# EDev.net
KiCad netlist of a schematic drawn in EasyEDA Pro
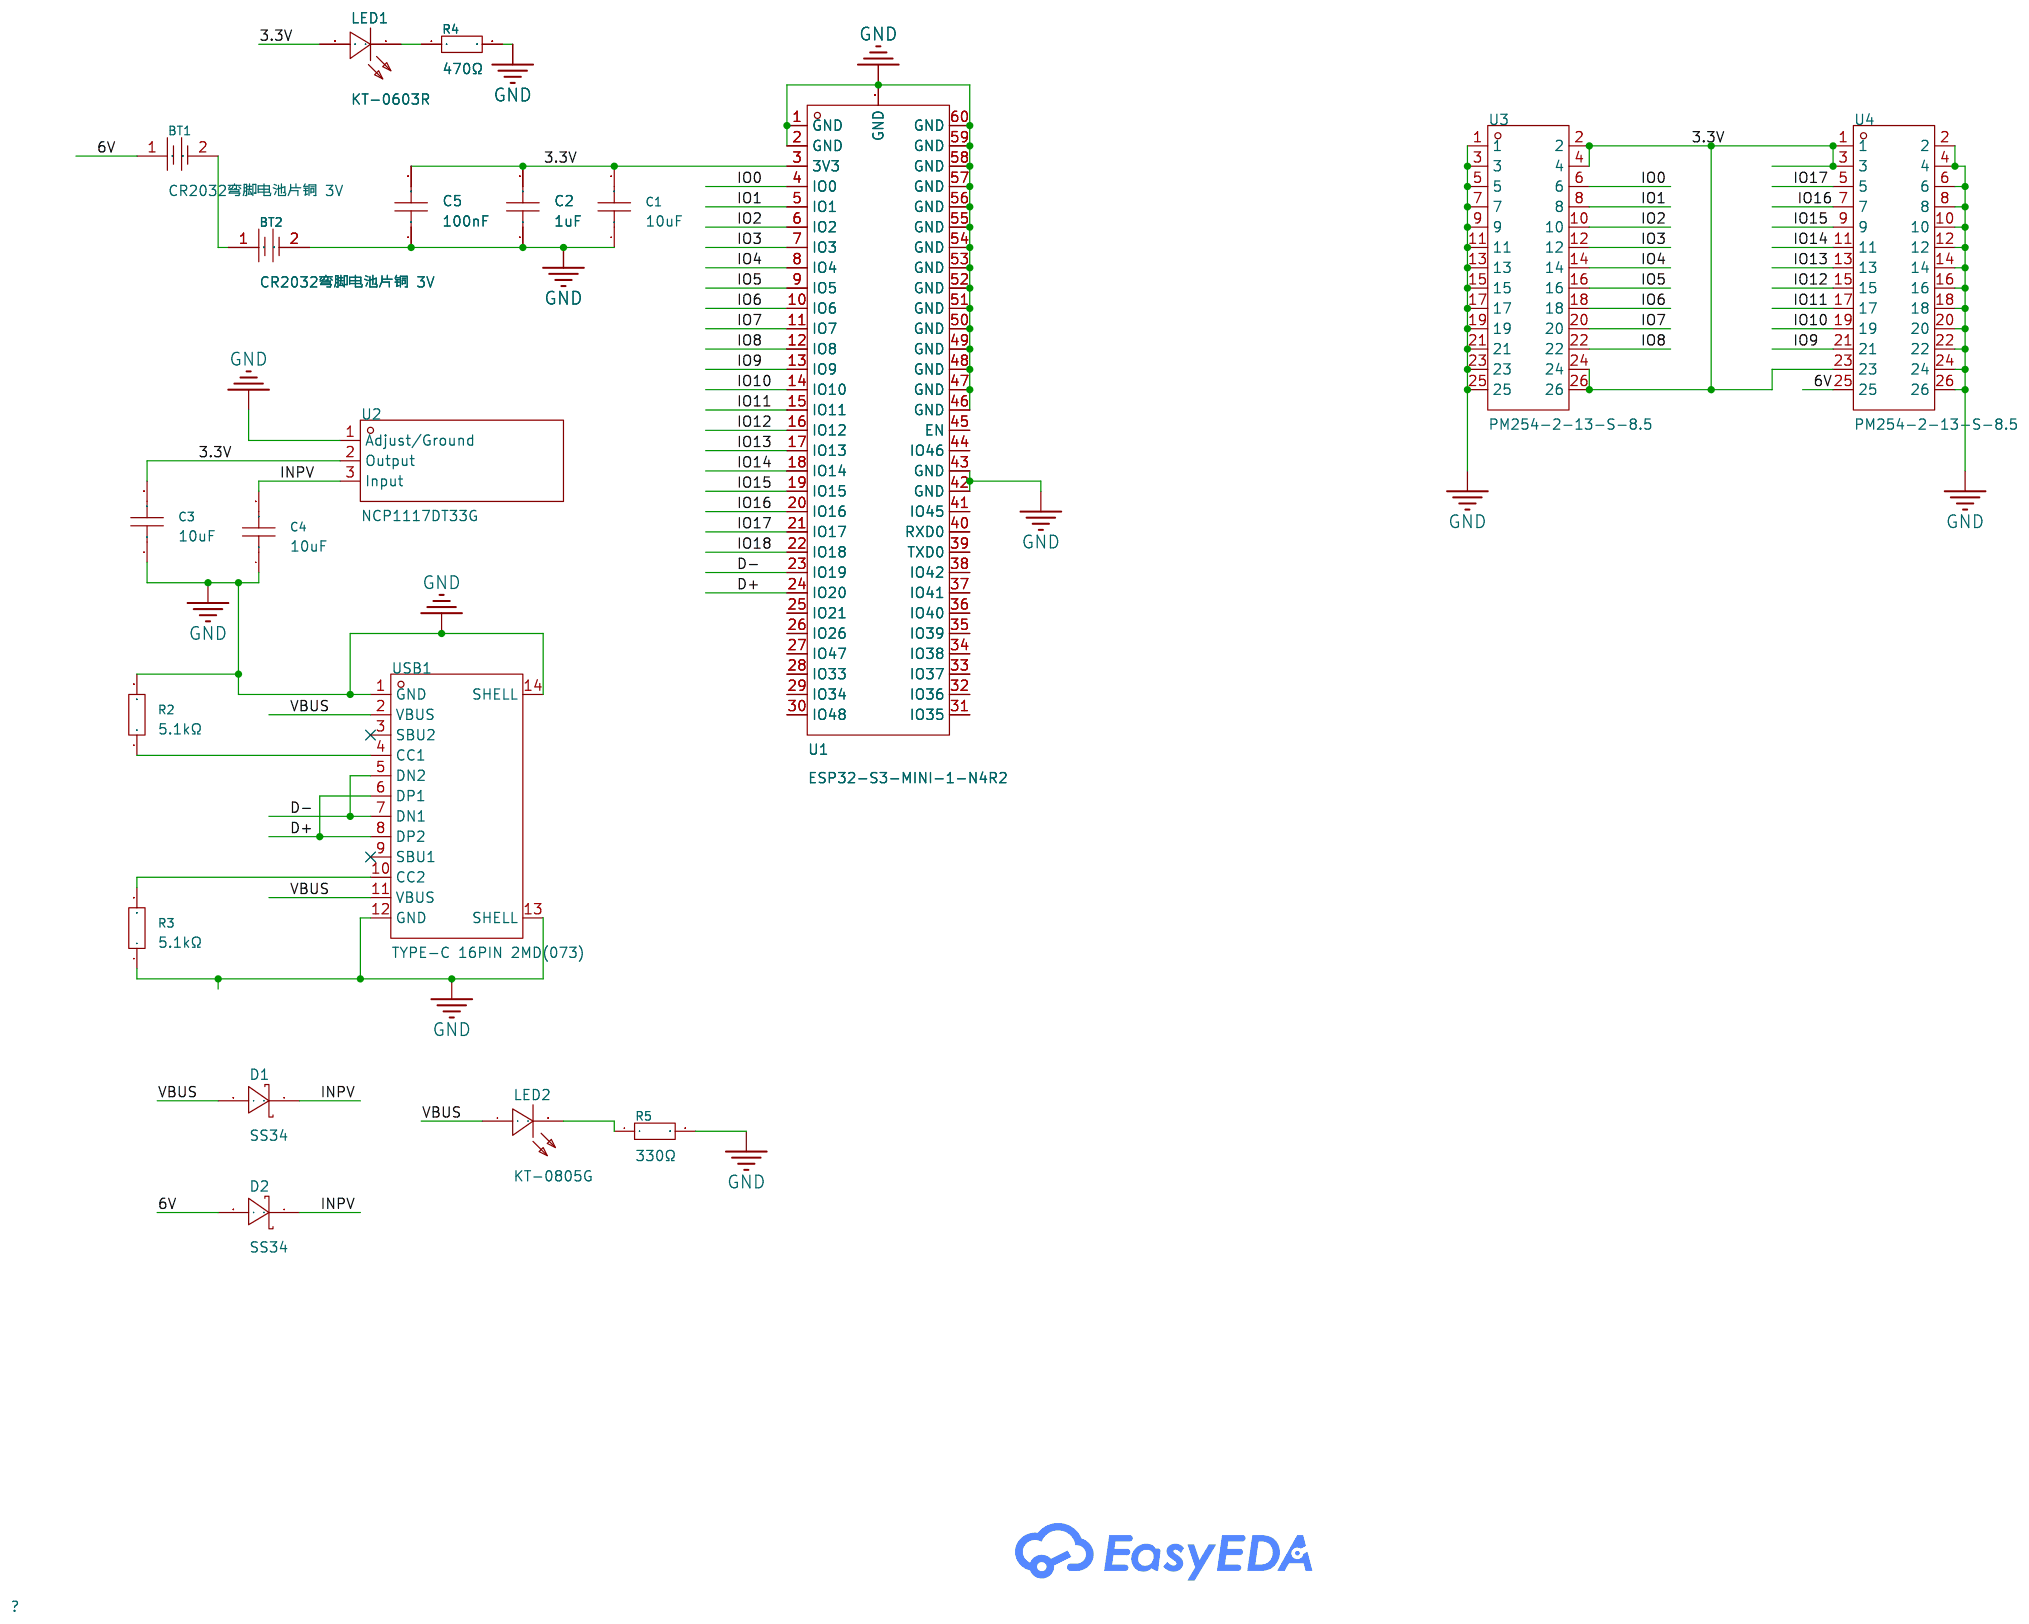
[diagram p0: schematic sheet]

(export (version "E")
  (design (tool "Eeschema 10.0.6"))
  (components
    (comp (ref "BT1")
      (value "CR2032弯脚电池片铜 3V")
      (footprint "easyedapro:BAT-SMD_CR2032-3V")
      (fields (field (name "Manufacturer") "Q&J"))
      (libsource (lib "easyedapro") (part "C70373"))
    )
    (comp (ref "BT2")
      (value "CR2032弯脚电池片铜 3V")
      (footprint "easyedapro:BAT-SMD_CR2032-3V")
      (fields (field (name "Manufacturer") "Q&J"))
      (libsource (lib "easyedapro") (part "C70373"))
    )
    (comp (ref "C1")
      (value "10uF")
      (footprint "easyedapro:C0603")
      (fields
        (field (name "Manufacturer Part") "CL10A106MA8NRNC")
        (field (name "Manufacturer") "SAMSUNG(三星)")
      )
      (libsource (lib "easyedapro") (part "CL10A106MA8NRNC"))
    )
    (comp (ref "C2")
      (value "1uF")
      (footprint "easyedapro:C0603")
      (fields
        (field (name "Manufacturer Part") "CL10A105KB8NNNC")
        (field (name "Manufacturer") "SAMSUNG(三星)")
      )
      (libsource (lib "easyedapro") (part "CL10A105KB8NNNC"))
    )
    (comp (ref "C3")
      (value "10uF")
      (footprint "easyedapro:C0603")
      (fields
        (field (name "Manufacturer Part") "CL10A106MA8NRNC")
        (field (name "Manufacturer") "SAMSUNG(三星)")
      )
      (libsource (lib "easyedapro") (part "CL10A106MA8NRNC"))
    )
    (comp (ref "C4")
      (value "10uF")
      (footprint "easyedapro:C0603")
      (fields
        (field (name "Manufacturer Part") "CL10A106MA8NRNC")
        (field (name "Manufacturer") "SAMSUNG(三星)")
      )
      (libsource (lib "easyedapro") (part "CL10A106MA8NRNC"))
    )
    (comp (ref "C5")
      (value "100nF")
      (footprint "easyedapro:C0402")
      (fields
        (field (name "Manufacturer Part") "CL05B104KO5NNNC")
        (field (name "Manufacturer") "SAMSUNG(三星)")
      )
      (libsource (lib "easyedapro") (part "CL05B104KO5NNNC"))
    )
    (comp (ref "D1")
      (value "SS34")
      (footprint "easyedapro:SMA_L4.3-W2.6-LS5.2-RD")
      (fields (field (name "Manufacturer") "MDD(辰达半导体)"))
      (libsource (lib "easyedapro") (part "SS34_C8678"))
    )
    (comp (ref "D2")
      (value "SS34")
      (footprint "easyedapro:SMA_L4.3-W2.6-LS5.2-RD")
      (fields (field (name "Manufacturer") "MDD(辰达半导体)"))
      (libsource (lib "easyedapro") (part "SS34_C8678"))
    )
    (comp (ref "LED1")
      (value "KT-0603R")
      (footprint "easyedapro:LED0603-RD")
      (fields (field (name "Manufacturer") "KENTO"))
      (libsource (lib "easyedapro") (part "KT-0603R"))
    )
    (comp (ref "LED2")
      (value "KT-0805G")
      (footprint "easyedapro:LED0805-R-RD")
      (fields (field (name "Manufacturer") "KENTO"))
      (libsource (lib "easyedapro") (part "0805G (Green)"))
    )
    (comp (ref "R2")
      (value "5.1kΩ")
      (footprint "easyedapro:R0402")
      (fields
        (field (name "Manufacturer Part") "0402WGF5101TCE")
        (field (name "Manufacturer") "UNI-ROYAL(厚声)")
      )
      (libsource (lib "easyedapro") (part "0402WGF5101TCE"))
    )
    (comp (ref "R3")
      (value "5.1kΩ")
      (footprint "easyedapro:R0402")
      (fields
        (field (name "Manufacturer Part") "0402WGF5101TCE")
        (field (name "Manufacturer") "UNI-ROYAL(厚声)")
      )
      (libsource (lib "easyedapro") (part "0402WGF5101TCE"))
    )
    (comp (ref "R4")
      (value "470Ω")
      (footprint "easyedapro:R0805")
      (fields
        (field (name "Manufacturer Part") "0805W8F4700T5E")
        (field (name "Manufacturer") "UNI-ROYAL(厚声)")
      )
      (libsource (lib "easyedapro") (part "0805W8F4700T5E"))
    )
    (comp (ref "R5")
      (value "330Ω")
      (footprint "easyedapro:R0805")
      (fields
        (field (name "Manufacturer Part") "0805W8F3300T5E")
        (field (name "Manufacturer") "UNI-ROYAL(厚声)")
      )
      (libsource (lib "easyedapro") (part "0805W8F3300T5E"))
    )
    (comp (ref "U1")
      (value "ESP32-S3-MINI-1-N4R2")
      (footprint "easyedapro:BULETM-SMD_ESP32-S3-MINI-1-N8")
      (description "Antenna Type:On-Board PCB Antenna")
      (fields (field (name "Manufacturer") "ESPRESSIF(乐鑫)"))
      (libsource (lib "easyedapro") (part "ESP32-S3-MINI-1-N4R2"))
    )
    (comp (ref "U2")
      (value "NCP1117DT33G")
      (footprint "easyedapro:TO-252_L6.5-W6.1-P4.58-LS9.9-BR")
      (fields (field (name "Manufacturer") "onsemi(安森美)"))
      (libsource (lib "easyedapro") (part "NCP1117DT33G"))
    )
    (comp (ref "U3")
      (value "PM254-2-13-S-8.5")
      (footprint "easyedapro:HDR-SMD_26P-P2.54-V-F-R2-C13-LS7.2")
      (fields (field (name "Manufacturer") "HCTL(华灿天禄)"))
      (libsource (lib "easyedapro") (part "PM254-2-13-S-8.5"))
    )
    (comp (ref "U4")
      (value "PM254-2-13-S-8.5")
      (footprint "easyedapro:HDR-SMD_26P-P2.54-V-F-R2-C13-LS7.2")
      (fields (field (name "Manufacturer") "HCTL(华灿天禄)"))
      (libsource (lib "easyedapro") (part "PM254-2-13-S-8.5"))
    )
    (comp (ref "USB1")
      (value "TYPE-C 16PIN 2MD(073)")
      (footprint "easyedapro:USB-C-SMD_TYPE-C-6PIN-2MD-073")
      (fields (field (name "Manufacturer") "SHOU HAN(首韩)"))
      (libsource (lib "easyedapro") (part "TYPE-C 16PIN 2MD(073)"))
    )
  )
  (nets
    (net (code "1") (name "/3.3V") (class "Default")
      (node (ref "C1") (pin "2") (pinfunction "2_2") (pintype "input"))
      (node (ref "C2") (pin "2") (pinfunction "2_2") (pintype "unspecified"))
      (node (ref "C3") (pin "2") (pinfunction "2_2") (pintype "input"))
      (node (ref "C5") (pin "2") (pinfunction "2_2") (pintype "unspecified"))
      (node (ref "LED1") (pin "2") (pinfunction "A_2") (pintype "unspecified"))
      (node (ref "U1") (pin "3") (pinfunction "3V3_3") (pintype "unspecified"))
      (node (ref "U2") (pin "2") (pinfunction "Output_2") (pintype "unspecified"))
      (node (ref "U3") (pin "2") (pinfunction "2_2") (pintype "unspecified"))
      (node (ref "U3") (pin "24") (pinfunction "24_24") (pintype "unspecified"))
      (node (ref "U3") (pin "26") (pinfunction "26_26") (pintype "unspecified"))
      (node (ref "U3") (pin "4") (pinfunction "4_4") (pintype "unspecified"))
      (node (ref "U4") (pin "1") (pinfunction "1_1") (pintype "unspecified"))
      (node (ref "U4") (pin "23") (pinfunction "23_23") (pintype "unspecified"))
      (node (ref "U4") (pin "3") (pinfunction "3_3") (pintype "unspecified"))
    )
    (net (code "2") (name "/6V") (class "Default")
      (node (ref "BT1") (pin "1") (pinfunction "1_1") (pintype "input"))
      (node (ref "D2") (pin "2") (pinfunction "A_2") (pintype "unspecified"))
      (node (ref "U4") (pin "25") (pinfunction "25_25") (pintype "unspecified"))
    )
    (net (code "3") (name "/D+") (class "Default")
      (node (ref "U1") (pin "24") (pinfunction "IO20_24") (pintype "unspecified"))
      (node (ref "USB1") (pin "6") (pinfunction "DP1_6") (pintype "unspecified"))
      (node (ref "USB1") (pin "8") (pinfunction "DP2_8") (pintype "unspecified"))
    )
    (net (code "4") (name "/D-") (class "Default")
      (node (ref "U1") (pin "23") (pinfunction "IO19_23") (pintype "unspecified"))
      (node (ref "USB1") (pin "5") (pinfunction "DN2_5") (pintype "unspecified"))
      (node (ref "USB1") (pin "7") (pinfunction "DN1_7") (pintype "unspecified"))
    )
    (net (code "5") (name "/INPV") (class "Default")
      (node (ref "C4") (pin "2") (pinfunction "2_2") (pintype "input"))
      (node (ref "D1") (pin "1") (pinfunction "K_1") (pintype "unspecified"))
      (node (ref "D2") (pin "1") (pinfunction "K_1") (pintype "unspecified"))
      (node (ref "U2") (pin "3") (pinfunction "Input_3") (pintype "unspecified"))
    )
    (net (code "6") (name "/IO0") (class "Default")
      (node (ref "U1") (pin "4") (pinfunction "IO0_4") (pintype "unspecified"))
      (node (ref "U3") (pin "6") (pinfunction "6_6") (pintype "unspecified"))
    )
    (net (code "7") (name "/IO1") (class "Default")
      (node (ref "U1") (pin "5") (pinfunction "IO1_5") (pintype "unspecified"))
      (node (ref "U3") (pin "8") (pinfunction "8_8") (pintype "unspecified"))
    )
    (net (code "8") (name "/IO2") (class "Default")
      (node (ref "U1") (pin "6") (pinfunction "IO2_6") (pintype "unspecified"))
      (node (ref "U3") (pin "10") (pinfunction "10_10") (pintype "unspecified"))
    )
    (net (code "9") (name "/IO3") (class "Default")
      (node (ref "U1") (pin "7") (pinfunction "IO3_7") (pintype "unspecified"))
      (node (ref "U3") (pin "12") (pinfunction "12_12") (pintype "unspecified"))
    )
    (net (code "10") (name "/IO4") (class "Default")
      (node (ref "U1") (pin "8") (pinfunction "IO4_8") (pintype "unspecified"))
      (node (ref "U3") (pin "14") (pinfunction "14_14") (pintype "unspecified"))
    )
    (net (code "11") (name "/IO5") (class "Default")
      (node (ref "U1") (pin "9") (pinfunction "IO5_9") (pintype "unspecified"))
      (node (ref "U3") (pin "16") (pinfunction "16_16") (pintype "unspecified"))
    )
    (net (code "12") (name "/IO6") (class "Default")
      (node (ref "U1") (pin "10") (pinfunction "IO6_10") (pintype "unspecified"))
      (node (ref "U3") (pin "18") (pinfunction "18_18") (pintype "unspecified"))
    )
    (net (code "13") (name "/IO7") (class "Default")
      (node (ref "U1") (pin "11") (pinfunction "IO7_11") (pintype "unspecified"))
      (node (ref "U3") (pin "20") (pinfunction "20_20") (pintype "unspecified"))
    )
    (net (code "14") (name "/IO8") (class "Default")
      (node (ref "U1") (pin "12") (pinfunction "IO8_12") (pintype "unspecified"))
      (node (ref "U3") (pin "22") (pinfunction "22_22") (pintype "unspecified"))
    )
    (net (code "15") (name "/IO9") (class "Default")
      (node (ref "U1") (pin "13") (pinfunction "IO9_13") (pintype "unspecified"))
      (node (ref "U4") (pin "21") (pinfunction "21_21") (pintype "unspecified"))
    )
    (net (code "16") (name "/IO10") (class "Default")
      (node (ref "U1") (pin "14") (pinfunction "IO10_14") (pintype "unspecified"))
      (node (ref "U4") (pin "19") (pinfunction "19_19") (pintype "unspecified"))
    )
    (net (code "17") (name "/IO11") (class "Default")
      (node (ref "U1") (pin "15") (pinfunction "IO11_15") (pintype "unspecified"))
      (node (ref "U4") (pin "17") (pinfunction "17_17") (pintype "unspecified"))
    )
    (net (code "18") (name "/IO12") (class "Default")
      (node (ref "U1") (pin "16") (pinfunction "IO12_16") (pintype "unspecified"))
      (node (ref "U4") (pin "15") (pinfunction "15_15") (pintype "unspecified"))
    )
    (net (code "19") (name "/IO13") (class "Default")
      (node (ref "U1") (pin "17") (pinfunction "IO13_17") (pintype "unspecified"))
      (node (ref "U4") (pin "13") (pinfunction "13_13") (pintype "unspecified"))
    )
    (net (code "20") (name "/IO14") (class "Default")
      (node (ref "U1") (pin "18") (pinfunction "IO14_18") (pintype "unspecified"))
      (node (ref "U4") (pin "11") (pinfunction "11_11") (pintype "unspecified"))
    )
    (net (code "21") (name "/IO15") (class "Default")
      (node (ref "U1") (pin "19") (pinfunction "IO15_19") (pintype "unspecified"))
      (node (ref "U4") (pin "9") (pinfunction "9_9") (pintype "unspecified"))
    )
    (net (code "22") (name "/IO16") (class "Default")
      (node (ref "U1") (pin "20") (pinfunction "IO16_20") (pintype "unspecified"))
      (node (ref "U4") (pin "7") (pinfunction "7_7") (pintype "unspecified"))
    )
    (net (code "23") (name "/IO17") (class "Default")
      (node (ref "U1") (pin "21") (pinfunction "IO17_21") (pintype "unspecified"))
      (node (ref "U4") (pin "5") (pinfunction "5_5") (pintype "unspecified"))
    )
    (net (code "24") (name "/IO18") (class "Default")
      (node (ref "U1") (pin "22") (pinfunction "IO18_22") (pintype "unspecified"))
    )
    (net (code "25") (name "/VBUS") (class "Default")
      (node (ref "D1") (pin "2") (pinfunction "A_2") (pintype "unspecified"))
      (node (ref "LED2") (pin "1") (pinfunction "A_1") (pintype "unspecified"))
      (node (ref "USB1") (pin "11") (pinfunction "VBUS_11") (pintype "unspecified"))
      (node (ref "USB1") (pin "2") (pinfunction "VBUS_2") (pintype "unspecified"))
    )
    (net (code "26") (name "GND") (class "Default")
      (node (ref "BT2") (pin "2") (pinfunction "2_2") (pintype "input"))
      (node (ref "C1") (pin "1") (pinfunction "1_1") (pintype "input"))
      (node (ref "C2") (pin "1") (pinfunction "1_1") (pintype "unspecified"))
      (node (ref "C3") (pin "1") (pinfunction "1_1") (pintype "input"))
      (node (ref "C4") (pin "1") (pinfunction "1_1") (pintype "input"))
      (node (ref "C5") (pin "1") (pinfunction "1_1") (pintype "unspecified"))
      (node (ref "R2") (pin "2") (pinfunction "2_2") (pintype "input"))
      (node (ref "R3") (pin "1") (pinfunction "1_1") (pintype "input"))
      (node (ref "R4") (pin "2") (pinfunction "2_2") (pintype "input"))
      (node (ref "R5") (pin "2") (pinfunction "2_2") (pintype "input"))
      (node (ref "U1") (pin "1") (pinfunction "GND_1") (pintype "unspecified"))
      (node (ref "U1") (pin "2") (pinfunction "GND_2") (pintype "unspecified"))
      (node (ref "U1") (pin "42") (pinfunction "GND_42") (pintype "unspecified"))
      (node (ref "U1") (pin "43") (pinfunction "GND_43") (pintype "unspecified"))
      (node (ref "U1") (pin "46") (pinfunction "GND_46") (pintype "unspecified"))
      (node (ref "U1") (pin "47") (pinfunction "GND_47") (pintype "unspecified"))
      (node (ref "U1") (pin "48") (pinfunction "GND_48") (pintype "unspecified"))
      (node (ref "U1") (pin "49") (pinfunction "GND_49") (pintype "unspecified"))
      (node (ref "U1") (pin "50") (pinfunction "GND_50") (pintype "unspecified"))
      (node (ref "U1") (pin "51") (pinfunction "GND_51") (pintype "unspecified"))
      (node (ref "U1") (pin "52") (pinfunction "GND_52") (pintype "unspecified"))
      (node (ref "U1") (pin "53") (pinfunction "GND_53") (pintype "unspecified"))
      (node (ref "U1") (pin "54") (pinfunction "GND_54") (pintype "unspecified"))
      (node (ref "U1") (pin "55") (pinfunction "GND_55") (pintype "unspecified"))
      (node (ref "U1") (pin "56") (pinfunction "GND_56") (pintype "unspecified"))
      (node (ref "U1") (pin "57") (pinfunction "GND_57") (pintype "unspecified"))
      (node (ref "U1") (pin "58") (pinfunction "GND_58") (pintype "unspecified"))
      (node (ref "U1") (pin "59") (pinfunction "GND_59") (pintype "unspecified"))
      (node (ref "U1") (pin "60") (pinfunction "GND_60") (pintype "unspecified"))
      (node (ref "U1") (pin "GND") (pinfunction "GND_GND") (pintype "unspecified"))
      (node (ref "U2") (pin "1") (pinfunction "Adjust/Ground_1") (pintype "unspecified"))
      (node (ref "U3") (pin "1") (pinfunction "1_1") (pintype "unspecified"))
      (node (ref "U3") (pin "11") (pinfunction "11_11") (pintype "unspecified"))
      (node (ref "U3") (pin "13") (pinfunction "13_13") (pintype "unspecified"))
      (node (ref "U3") (pin "15") (pinfunction "15_15") (pintype "unspecified"))
      (node (ref "U3") (pin "17") (pinfunction "17_17") (pintype "unspecified"))
      (node (ref "U3") (pin "19") (pinfunction "19_19") (pintype "unspecified"))
      (node (ref "U3") (pin "21") (pinfunction "21_21") (pintype "unspecified"))
      (node (ref "U3") (pin "23") (pinfunction "23_23") (pintype "unspecified"))
      (node (ref "U3") (pin "25") (pinfunction "25_25") (pintype "unspecified"))
      (node (ref "U3") (pin "3") (pinfunction "3_3") (pintype "unspecified"))
      (node (ref "U3") (pin "5") (pinfunction "5_5") (pintype "unspecified"))
      (node (ref "U3") (pin "7") (pinfunction "7_7") (pintype "unspecified"))
      (node (ref "U3") (pin "9") (pinfunction "9_9") (pintype "unspecified"))
      (node (ref "U4") (pin "10") (pinfunction "10_10") (pintype "unspecified"))
      (node (ref "U4") (pin "12") (pinfunction "12_12") (pintype "unspecified"))
      (node (ref "U4") (pin "14") (pinfunction "14_14") (pintype "unspecified"))
      (node (ref "U4") (pin "16") (pinfunction "16_16") (pintype "unspecified"))
      (node (ref "U4") (pin "18") (pinfunction "18_18") (pintype "unspecified"))
      (node (ref "U4") (pin "2") (pinfunction "2_2") (pintype "unspecified"))
      (node (ref "U4") (pin "20") (pinfunction "20_20") (pintype "unspecified"))
      (node (ref "U4") (pin "22") (pinfunction "22_22") (pintype "unspecified"))
      (node (ref "U4") (pin "24") (pinfunction "24_24") (pintype "unspecified"))
      (node (ref "U4") (pin "26") (pinfunction "26_26") (pintype "unspecified"))
      (node (ref "U4") (pin "4") (pinfunction "4_4") (pintype "unspecified"))
      (node (ref "U4") (pin "6") (pinfunction "6_6") (pintype "unspecified"))
      (node (ref "U4") (pin "8") (pinfunction "8_8") (pintype "unspecified"))
      (node (ref "USB1") (pin "1") (pinfunction "GND_1") (pintype "unspecified"))
      (node (ref "USB1") (pin "12") (pinfunction "GND_12") (pintype "unspecified"))
      (node (ref "USB1") (pin "13") (pinfunction "SHELL_13") (pintype "unspecified"))
      (node (ref "USB1") (pin "14") (pinfunction "SHELL_14") (pintype "unspecified"))
    )
    (net (code "27") (name "Net-(BT1-Pad2)") (class "Default")
      (node (ref "BT1") (pin "2") (pinfunction "2_2") (pintype "input"))
      (node (ref "BT2") (pin "1") (pinfunction "1_1") (pintype "input"))
    )
    (net (code "28") (name "Net-(LED1-K)") (class "Default")
      (node (ref "LED1") (pin "1") (pinfunction "K_1") (pintype "unspecified"))
      (node (ref "R4") (pin "1") (pinfunction "1_1") (pintype "input"))
    )
    (net (code "29") (name "Net-(LED2-K)") (class "Default")
      (node (ref "LED2") (pin "2") (pinfunction "K_2") (pintype "unspecified"))
      (node (ref "R5") (pin "1") (pinfunction "1_1") (pintype "input"))
    )
    (net (code "30") (name "Net-(USB1-CC1)") (class "Default")
      (node (ref "R2") (pin "1") (pinfunction "1_1") (pintype "input"))
      (node (ref "USB1") (pin "4") (pinfunction "CC1_4") (pintype "unspecified"))
    )
    (net (code "31") (name "Net-(USB1-CC2)") (class "Default")
      (node (ref "R3") (pin "2") (pinfunction "2_2") (pintype "input"))
      (node (ref "USB1") (pin "10") (pinfunction "CC2_10") (pintype "unspecified"))
    )
    (net (code "32") (name "unconnected-(U1-EN-Pad45)") (class "Default")
      (node (ref "U1") (pin "45") (pinfunction "EN_45") (pintype "unspecified"))
    )
    (net (code "33") (name "unconnected-(U1-IO21-Pad25)") (class "Default")
      (node (ref "U1") (pin "25") (pinfunction "IO21_25") (pintype "unspecified"))
    )
    (net (code "34") (name "unconnected-(U1-IO26-Pad26)") (class "Default")
      (node (ref "U1") (pin "26") (pinfunction "IO26_26") (pintype "unspecified"))
    )
    (net (code "35") (name "unconnected-(U1-IO33-Pad28)") (class "Default")
      (node (ref "U1") (pin "28") (pinfunction "IO33_28") (pintype "unspecified"))
    )
    (net (code "36") (name "unconnected-(U1-IO34-Pad29)") (class "Default")
      (node (ref "U1") (pin "29") (pinfunction "IO34_29") (pintype "unspecified"))
    )
    (net (code "37") (name "unconnected-(U1-IO35-Pad31)") (class "Default")
      (node (ref "U1") (pin "31") (pinfunction "IO35_31") (pintype "unspecified"))
    )
    (net (code "38") (name "unconnected-(U1-IO36-Pad32)") (class "Default")
      (node (ref "U1") (pin "32") (pinfunction "IO36_32") (pintype "unspecified"))
    )
    (net (code "39") (name "unconnected-(U1-IO37-Pad33)") (class "Default")
      (node (ref "U1") (pin "33") (pinfunction "IO37_33") (pintype "unspecified"))
    )
    (net (code "40") (name "unconnected-(U1-IO38-Pad34)") (class "Default")
      (node (ref "U1") (pin "34") (pinfunction "IO38_34") (pintype "unspecified"))
    )
    (net (code "41") (name "unconnected-(U1-IO39-Pad35)") (class "Default")
      (node (ref "U1") (pin "35") (pinfunction "IO39_35") (pintype "unspecified"))
    )
    (net (code "42") (name "unconnected-(U1-IO40-Pad36)") (class "Default")
      (node (ref "U1") (pin "36") (pinfunction "IO40_36") (pintype "unspecified"))
    )
    (net (code "43") (name "unconnected-(U1-IO41-Pad37)") (class "Default")
      (node (ref "U1") (pin "37") (pinfunction "IO41_37") (pintype "unspecified"))
    )
    (net (code "44") (name "unconnected-(U1-IO42-Pad38)") (class "Default")
      (node (ref "U1") (pin "38") (pinfunction "IO42_38") (pintype "unspecified"))
    )
    (net (code "45") (name "unconnected-(U1-IO45-Pad41)") (class "Default")
      (node (ref "U1") (pin "41") (pinfunction "IO45_41") (pintype "unspecified"))
    )
    (net (code "46") (name "unconnected-(U1-IO46-Pad44)") (class "Default")
      (node (ref "U1") (pin "44") (pinfunction "IO46_44") (pintype "unspecified"))
    )
    (net (code "47") (name "unconnected-(U1-IO47-Pad27)") (class "Default")
      (node (ref "U1") (pin "27") (pinfunction "IO47_27") (pintype "unspecified"))
    )
    (net (code "48") (name "unconnected-(U1-IO48-Pad30)") (class "Default")
      (node (ref "U1") (pin "30") (pinfunction "IO48_30") (pintype "unspecified"))
    )
    (net (code "49") (name "unconnected-(U1-RXD0-Pad40)") (class "Default")
      (node (ref "U1") (pin "40") (pinfunction "RXD0_40") (pintype "unspecified"))
    )
    (net (code "50") (name "unconnected-(U1-TXD0-Pad39)") (class "Default")
      (node (ref "U1") (pin "39") (pinfunction "TXD0_39") (pintype "unspecified"))
    )
    (net (code "51") (name "unconnected-(USB1-SBU1-Pad9)") (class "Default")
      (node (ref "USB1") (pin "9") (pinfunction "SBU1_9") (pintype "unspecified+no_connect"))
    )
    (net (code "52") (name "unconnected-(USB1-SBU2-Pad3)") (class "Default")
      (node (ref "USB1") (pin "3") (pinfunction "SBU2_3") (pintype "unspecified+no_connect"))
    )
  )
)
